# dcdc_5v0_3v3.net
KiCad netlist of a schematic drawn in Altium Designer
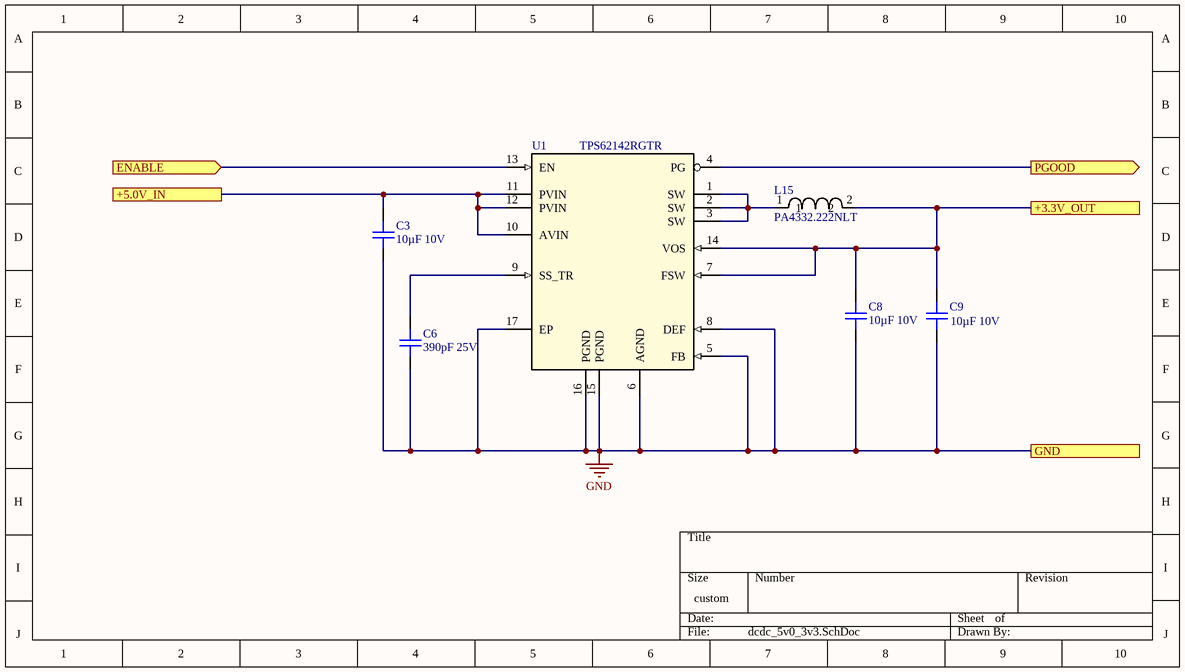
[diagram p0: dcdc_5v0_3v3.SchDoc]

(export (version "E")
  (design (tool "Eeschema 10.0.6"))
  (components
    (comp (ref "C3")
      (value "10µF 10V")
      (footprint "0805C")
      (description "Ceramic, 10µF, ±10%, 10V, X7R, –55 to 125°C, 0805 (2012),RoHS, Automotive")
      (fields (field (name "PART NUMBER") "GCJ21BR71A106KE01") (field (name "TOLERANCE") "±10%"))
      (libsource (lib "master-010106") (part "gen_C_ceramic_10u_10V_X7R_0805"))
    )
    (comp (ref "C6")
      (value "390pF 25V")
      (footprint "0402C")
      (description "Ceramic, 390pF, ±5%, 25V, C0G, 25 to 125°C, 0402 (1005),RoHS, Automotive")
      (fields (field (name "PART NUMBER") "GCM1555C1H180JA16#") (field (name "TOLERANCE") "±5%"))
      (libsource (lib "master-010106") (part "gen_C_ceramic_390p_25V_C0G_0402"))
    )
    (comp (ref "C8")
      (value "10µF 10V")
      (footprint "0805C")
      (description "Ceramic, 10µF, ±10%, 10V, X7R, –55 to 125°C, 0805 (2012),RoHS, Automotive")
      (fields (field (name "PART NUMBER") "GCJ21BR71A106KE01") (field (name "TOLERANCE") "±10%"))
      (libsource (lib "master-010106") (part "gen_C_ceramic_10u_10V_X7R_0805"))
    )
    (comp (ref "C9")
      (value "10µF 10V")
      (footprint "0805C")
      (description "Ceramic, 10µF, ±10%, 10V, X7R, –55 to 125°C, 0805 (2012),RoHS, Automotive")
      (fields (field (name "PART NUMBER") "GCJ21BR71A106KE01") (field (name "TOLERANCE") "±10%"))
      (libsource (lib "master-010106") (part "gen_C_ceramic_10u_10V_X7R_0805"))
    )
    (comp (ref "L15")
      (value "PA4332.222NLT")
      (footprint "PA4332")
      (description "Imported")
      (libsource (lib "ti-import") (part "PA4332.222NLT"))
    )
    (comp (ref "U1")
      (value "TPS62142RGTR")
      (footprint "RGT0016C")
      (description "Imported")
      (fields (field (name "MANUFACTURER") "Texas Instruments"))
      (libsource (lib "ti-import") (part "TPS62142RGTR"))
    )
  )
  (nets
    (net (code "1") (name "/+3.3V_OUT") (class "Default")
      (node (ref "C8") (pin "1") (pinfunction "1_1") (pintype "passive"))
      (node (ref "C9") (pin "1") (pinfunction "1_1") (pintype "passive"))
      (node (ref "L15") (pin "2") (pinfunction "2_2") (pintype "passive"))
      (node (ref "U1") (pin "14") (pinfunction "VOS_14") (pintype "input"))
      (node (ref "U1") (pin "7") (pinfunction "FSW_7") (pintype "input"))
    )
    (net (code "2") (name "/+5.0V_IN") (class "Default")
      (node (ref "C3") (pin "1") (pinfunction "1_1") (pintype "passive"))
      (node (ref "U1") (pin "10") (pinfunction "AVIN_10") (pintype "power_in"))
      (node (ref "U1") (pin "11") (pinfunction "PVIN_11") (pintype "power_in"))
      (node (ref "U1") (pin "12") (pinfunction "PVIN_12") (pintype "power_in"))
    )
    (net (code "3") (name "/ENABLE") (class "Default")
      (node (ref "U1") (pin "13") (pinfunction "EN_13") (pintype "input"))
    )
    (net (code "4") (name "/PGOOD") (class "Default")
      (node (ref "U1") (pin "4") (pinfunction "PG_4") (pintype "open_collector"))
    )
    (net (code "5") (name "GND") (class "Default")
      (node (ref "C3") (pin "2") (pinfunction "2_2") (pintype "passive"))
      (node (ref "C6") (pin "1") (pinfunction "1_1") (pintype "passive"))
      (node (ref "C8") (pin "2") (pinfunction "2_2") (pintype "passive"))
      (node (ref "C9") (pin "2") (pinfunction "2_2") (pintype "passive"))
      (node (ref "U1") (pin "15") (pinfunction "PGND_15") (pintype "power_in"))
      (node (ref "U1") (pin "16") (pinfunction "PGND_16") (pintype "power_in"))
      (node (ref "U1") (pin "17") (pinfunction "EP_17") (pintype "power_in"))
      (node (ref "U1") (pin "5") (pinfunction "FB_5") (pintype "input"))
      (node (ref "U1") (pin "6") (pinfunction "AGND_6") (pintype "power_in"))
      (node (ref "U1") (pin "8") (pinfunction "DEF_8") (pintype "input"))
    )
    (net (code "6") (name "Net-(L15-Pad1)") (class "Default")
      (node (ref "L15") (pin "1") (pinfunction "1_1") (pintype "passive"))
      (node (ref "U1") (pin "1") (pinfunction "SW_1") (pintype "power_in"))
      (node (ref "U1") (pin "2") (pinfunction "SW_2") (pintype "power_in"))
      (node (ref "U1") (pin "3") (pinfunction "SW_3") (pintype "power_in"))
    )
    (net (code "7") (name "Net-(U1-SS_TR)") (class "Default")
      (node (ref "C6") (pin "2") (pinfunction "2_2") (pintype "passive"))
      (node (ref "U1") (pin "9") (pinfunction "SS_TR_9") (pintype "input"))
    )
  )
)
